# Controller_Board_Interface.net
KiCad netlist of a schematic drawn in Altium Designer
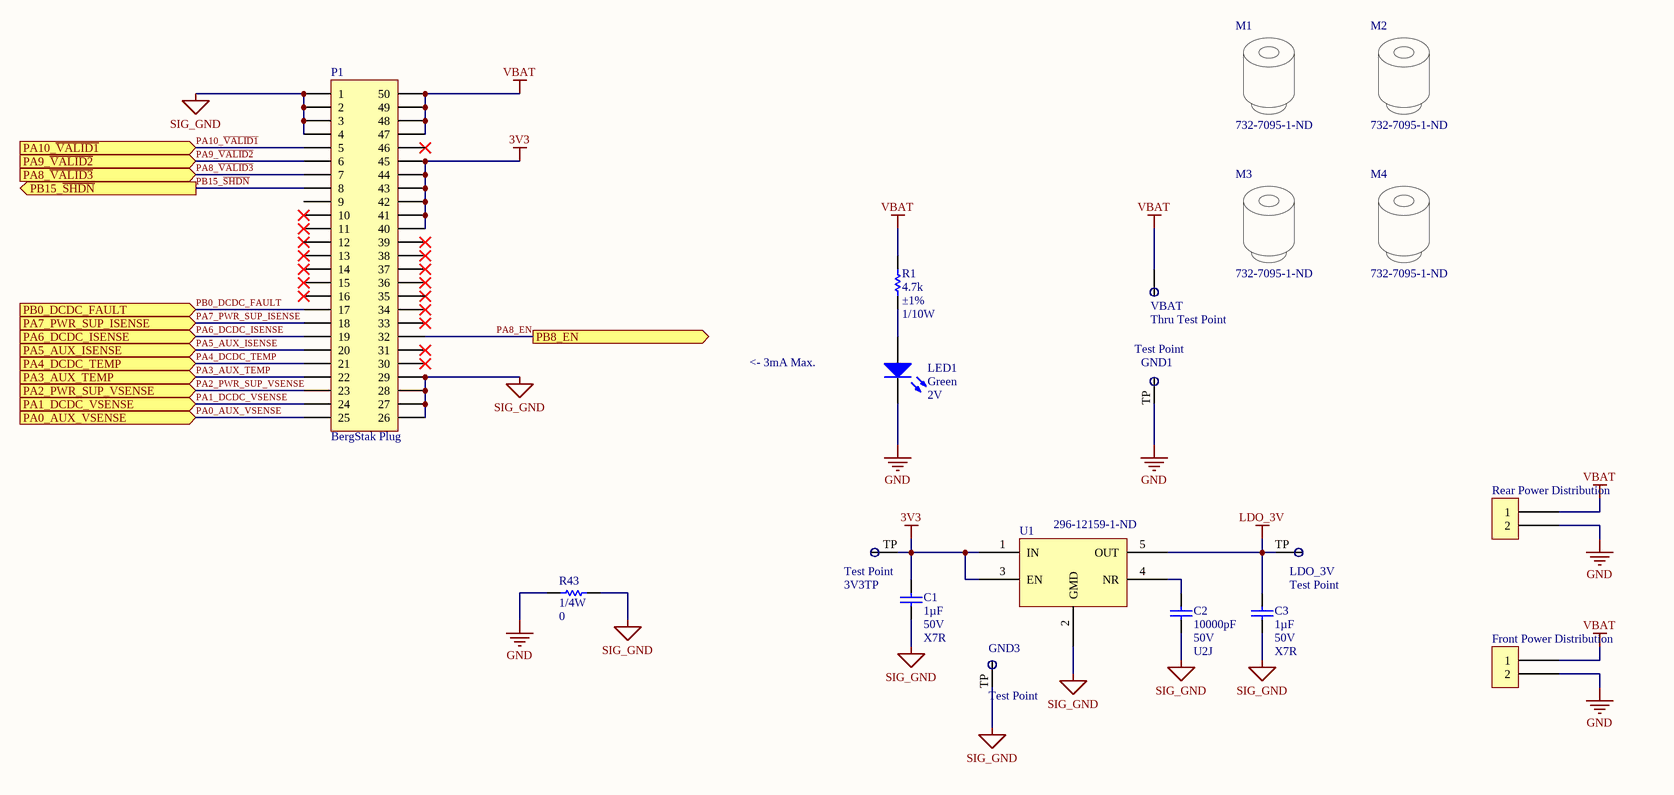
[diagram p0: Controller_Board_Interface.SchDoc]

(export (version "E")
  (design (tool "Eeschema 10.0.6"))
  (components
    (comp (ref "3V3TP")
      (value "Test Point")
      (footprint "Test Point")
      (libsource (lib "Schematic Diagrams") (part "Test Point"))
    )
    (comp (ref "C1")
      (value "CAP CER 1UF 50V 10% X7R 0603")
      (footprint "CAP, 0603")
      (description "1µF ±10% 50V Ceramic Capacitor X7R 0603 (1608 Metric)")
      (fields
        (field (name "TOLERANCE") "±10%")
        (field (name "CAPACITANCE") "1µF")
        (field (name "VOLTAGE") "50V")
        (field (name "TEMPERATURE COEFFICIENT") "X7R")
      )
      (libsource (lib "Schematic Diagrams") (part "CAP CER 1UF 50V 10% X7R 0603"))
    )
    (comp (ref "C2")
      (value "CAP CER 10nF 50V 5% X7R 0603")
      (footprint "CAP, 0603")
      (description "10000pF ±5% 50V Ceramic Capacitor U2J 0603 (1608 Metric)")
      (fields
        (field (name "TOLERANCE") "±5%")
        (field (name "CAPACITANCE") "10000pF")
        (field (name "VOLTAGE") "50V")
        (field (name "TEMPERATURE COEFFICIENT") "U2J")
      )
      (libsource (lib "Schematic Diagrams") (part "CAP CER 10nF 50V 5% X7R 0603"))
    )
    (comp (ref "C3")
      (value "CAP CER 1UF 50V 10% X7R 0603")
      (footprint "CAP, 0603")
      (description "1µF ±10% 50V Ceramic Capacitor X7R 0603 (1608 Metric)")
      (fields
        (field (name "TOLERANCE") "±10%")
        (field (name "CAPACITANCE") "1µF")
        (field (name "VOLTAGE") "50V")
        (field (name "TEMPERATURE COEFFICIENT") "X7R")
      )
      (libsource (lib "Schematic Diagrams") (part "CAP CER 1UF 50V 10% X7R 0603"))
    )
    (comp (ref "Front Power Distribution")
      (value "CONN HEADER TE  ELCON Mini 2POS PCB")
      (footprint "CONN HEADER TE  ELCON Mini 2POS PCB-Footprint-1")
      (description "CONN HEADER 2POS PCB")
      (libsource (lib "University of Waterloo - Solar Car Team") (part "CONN HEADER TE  ELCON Mini 2POS PCB"))
    )
    (comp (ref "GND1")
      (value "Test Point")
      (footprint "Test Point")
      (libsource (lib "Schematic Diagrams") (part "Test Point"))
    )
    (comp (ref "GND3")
      (value "Test Point")
      (footprint "Test Point")
      (libsource (lib "Schematic Diagrams") (part "Test Point"))
    )
    (comp (ref "LDO_3V")
      (value "Test Point")
      (footprint "Test Point")
      (libsource (lib "Schematic Diagrams") (part "Test Point"))
    )
    (comp (ref "LED1")
      (value "LED GREEN CLEAR 2V 0603")
      (footprint "LED_0603")
      (description "Green 572nm LED Indication - Discrete 2V 0603 (1608 Metric)")
      (fields
        (field (name "COLOR") "Green")
        (field (name "VOLTAGE - FORWARD (VF) (TYP)") "2V")
        (field (name "MANUFACTURER") "Wurth Electronics Inc.")
        (field (name "MANUFACTURER PART NUMBER") "150060VS75000")
      )
      (libsource (lib "Schematic Diagrams") (part "LED GREEN CLEAR 2V 0603"))
    )
    (comp (ref "M1")
      (value "STANDOFF RND M2.5X0.45 STEEL 5MM")
      (footprint "M2.5 Standoff")
      (fields
        (field (name "MANUFACTURER") "Wurth Electronics")
        (field (name "MANUFACTURER PART NUMBER") "9774050151R")
        (field (name "SUPPLIER PART NUMBER 1") "732-7095-1-ND")
      )
      (libsource (lib "Schematic Diagrams") (part "STANDOFF RND M2.5X0.45 STEEL 5MM"))
    )
    (comp (ref "M2")
      (value "STANDOFF RND M2.5X0.45 STEEL 5MM")
      (footprint "M2.5 Standoff")
      (fields
        (field (name "MANUFACTURER") "Wurth Electronics")
        (field (name "MANUFACTURER PART NUMBER") "9774050151R")
        (field (name "SUPPLIER PART NUMBER 1") "732-7095-1-ND")
      )
      (libsource (lib "Schematic Diagrams") (part "STANDOFF RND M2.5X0.45 STEEL 5MM"))
    )
    (comp (ref "M3")
      (value "STANDOFF RND M2.5X0.45 STEEL 5MM")
      (footprint "M2.5 Standoff")
      (fields
        (field (name "MANUFACTURER") "Wurth Electronics")
        (field (name "MANUFACTURER PART NUMBER") "9774050151R")
        (field (name "SUPPLIER PART NUMBER 1") "732-7095-1-ND")
      )
      (libsource (lib "Schematic Diagrams") (part "STANDOFF RND M2.5X0.45 STEEL 5MM"))
    )
    (comp (ref "M4")
      (value "STANDOFF RND M2.5X0.45 STEEL 5MM")
      (footprint "M2.5 Standoff")
      (fields
        (field (name "MANUFACTURER") "Wurth Electronics")
        (field (name "MANUFACTURER PART NUMBER") "9774050151R")
        (field (name "SUPPLIER PART NUMBER 1") "732-7095-1-ND")
      )
      (libsource (lib "Schematic Diagrams") (part "STANDOFF RND M2.5X0.45 STEEL 5MM"))
    )
    (comp (ref "P1")
      (value "CONN 50POS Bergstak Plug 0.02\"")
      (footprint "CONN, Bergstak 50 Pos Plug")
      (description "50 Position Connector Plug, Outer Shroud Contacts Surface Mount Gold")
      (fields (field (name "SERIES") "BergStak Plug"))
      (libsource (lib "Schematic Diagrams") (part "CONN 50POS Bergstak Plug 0.02{dblquote}"))
    )
    (comp (ref "R1")
      (value "RES 4.7K OHM 1% 1/10W 0603")
      (footprint "RES, 0603")
      (description "4.7k Ohm ±1% 0.1W, 1/10W Chip Resistor 0603 (1608 Metric) Moisture Resistant Thick Film")
      (fields
        (field (name "RESISTANCE (OHMS)") "4.7k")
        (field (name "TOLERANCE") "±1%")
        (field (name "POWER (WATTS)") "1/10W")
      )
      (libsource (lib "Schematic Diagrams") (part "RES 4.7K OHM 1% 1/10W 0603"))
    )
    (comp (ref "R43")
      (value "0")
      (footprint "RES, 0603")
      (description "RES SMD 0.0 OHM JUMPER 1/4W 0603")
      (fields
        (field (name "POWER (WATTS)") "1/4W")
        (field (name "Comment") "RES 0.0 OHM 1/4W 0603")
        (field (name "SOURCE") "Schematic Diagrams.SchLib")
      )
      (libsource (lib "University of Waterloo - Solar Car Team") (part "Symbol"))
    )
    (comp (ref "Rear Power Distribution")
      (value "CONN HEADER TE  ELCON Mini 2POS PCB")
      (footprint "CONN HEADER TE  ELCON Mini 2POS PCB-Footprint-1")
      (description "CONN HEADER 2POS PCB")
      (libsource (lib "University of Waterloo - Solar Car Team") (part "CONN HEADER TE  ELCON Mini 2POS PCB"))
    )
    (comp (ref "U1")
      (value "IC REG LINEAR 3V 200MA SOT23-5")
      (footprint "SOT95P280X145-5N")
      (description "Linear Voltage Regulator IC 1 Output 200mA SOT-23-5")
      (fields (field (name "SUPPLIER PART NUMBER 1") "296-12159-1-ND"))
      (libsource (lib "Schematic Diagrams") (part "IC REG LINEAR 3V 200MA SOT23-5"))
    )
    (comp (ref "VBAT")
      (value "Thru Test Point")
      (footprint "Thru Test Point")
      (libsource (lib "Schematic Diagrams") (part "Thru Test Point"))
    )
  )
  (nets
    (net (code "1") (name "/PA0_AUX_VSENSE") (class "Default")
      (node (ref "P1") (pin "25") (pinfunction "25_25") (pintype "passive"))
    )
    (net (code "2") (name "/PA1_DCDC_VSENSE") (class "Default")
      (node (ref "P1") (pin "24") (pinfunction "24_24") (pintype "passive"))
    )
    (net (code "3") (name "/PA2_PWR_SUP_VSENSE") (class "Default")
      (node (ref "P1") (pin "23") (pinfunction "23_23") (pintype "passive"))
    )
    (net (code "4") (name "/PA3_AUX_TEMP") (class "Default")
      (node (ref "P1") (pin "22") (pinfunction "22_22") (pintype "passive"))
    )
    (net (code "5") (name "/PA4_DCDC_TEMP") (class "Default")
      (node (ref "P1") (pin "21") (pinfunction "21_21") (pintype "passive"))
    )
    (net (code "6") (name "/PA5_AUX_ISENSE") (class "Default")
      (node (ref "P1") (pin "20") (pinfunction "20_20") (pintype "passive"))
    )
    (net (code "7") (name "/PA6_DCDC_ISENSE") (class "Default")
      (node (ref "P1") (pin "19") (pinfunction "19_19") (pintype "passive"))
    )
    (net (code "8") (name "/PA7_PWR_SUP_ISENSE") (class "Default")
      (node (ref "P1") (pin "18") (pinfunction "18_18") (pintype "passive"))
    )
    (net (code "9") (name "/PA8_EN") (class "Default")
      (node (ref "P1") (pin "32") (pinfunction "32_32") (pintype "passive"))
    )
    (net (code "10") (name "/PA8_~{VALID3}") (class "Default")
      (node (ref "P1") (pin "7") (pinfunction "7_7") (pintype "passive"))
    )
    (net (code "11") (name "/PA9_~{VALID2}") (class "Default")
      (node (ref "P1") (pin "6") (pinfunction "6_6") (pintype "passive"))
    )
    (net (code "12") (name "/PA10_~{VALID1}") (class "Default")
      (node (ref "P1") (pin "5") (pinfunction "5_5") (pintype "passive"))
    )
    (net (code "13") (name "/PB0_DCDC_FAULT") (class "Default")
      (node (ref "P1") (pin "17") (pinfunction "17_17") (pintype "passive"))
    )
    (net (code "14") (name "/PB15_~{SHDN}") (class "Default")
      (node (ref "P1") (pin "8") (pinfunction "8_8") (pintype "passive"))
    )
    (net (code "15") (name "3V3") (class "Default")
      (node (ref "3V3TP") (pin "TP") (pinfunction "1_TP") (pintype "passive"))
      (node (ref "C1") (pin "1") (pinfunction "1_1") (pintype "passive"))
      (node (ref "P1") (pin "40") (pinfunction "40_40") (pintype "passive"))
      (node (ref "P1") (pin "41") (pinfunction "41_41") (pintype "passive"))
      (node (ref "P1") (pin "42") (pinfunction "42_42") (pintype "passive"))
      (node (ref "P1") (pin "43") (pinfunction "43_43") (pintype "passive"))
      (node (ref "P1") (pin "44") (pinfunction "44_44") (pintype "passive"))
      (node (ref "P1") (pin "45") (pinfunction "45_45") (pintype "passive"))
      (node (ref "U1") (pin "1") (pinfunction "IN_1") (pintype "passive"))
      (node (ref "U1") (pin "3") (pinfunction "EN_3") (pintype "passive"))
    )
    (net (code "16") (name "GND") (class "Default")
      (node (ref "Front Power Distribution") (pin "2") (pinfunction "2_2") (pintype "passive"))
      (node (ref "GND1") (pin "TP") (pinfunction "1_TP") (pintype "passive"))
      (node (ref "LED1") (pin "2") (pinfunction "K_2") (pintype "passive"))
      (node (ref "R43") (pin "1") (pinfunction "1_1") (pintype "passive"))
      (node (ref "Rear Power Distribution") (pin "2") (pinfunction "2_2") (pintype "passive"))
    )
    (net (code "17") (name "LDO_3V") (class "Default")
      (node (ref "C3") (pin "1") (pinfunction "1_1") (pintype "passive"))
      (node (ref "LDO_3V") (pin "TP") (pinfunction "1_TP") (pintype "passive"))
      (node (ref "U1") (pin "5") (pinfunction "OUT_5") (pintype "passive"))
    )
    (net (code "18") (name "Net-(LED1-A)") (class "Default")
      (node (ref "LED1") (pin "1") (pinfunction "A_1") (pintype "passive"))
      (node (ref "R1") (pin "2") (pinfunction "2_2") (pintype "passive"))
    )
    (net (code "19") (name "Net-(U1-NR)") (class "Default")
      (node (ref "C2") (pin "1") (pinfunction "1_1") (pintype "passive"))
      (node (ref "U1") (pin "4") (pinfunction "NR_4") (pintype "passive"))
    )
    (net (code "20") (name "SIG_GND") (class "Default")
      (node (ref "C1") (pin "2") (pinfunction "2_2") (pintype "passive"))
      (node (ref "C2") (pin "2") (pinfunction "2_2") (pintype "passive"))
      (node (ref "C3") (pin "2") (pinfunction "2_2") (pintype "passive"))
      (node (ref "GND3") (pin "TP") (pinfunction "1_TP") (pintype "passive"))
      (node (ref "P1") (pin "1") (pinfunction "1_1") (pintype "passive"))
      (node (ref "P1") (pin "2") (pinfunction "2_2") (pintype "passive"))
      (node (ref "P1") (pin "26") (pinfunction "26_26") (pintype "passive"))
      (node (ref "P1") (pin "27") (pinfunction "27_27") (pintype "passive"))
      (node (ref "P1") (pin "28") (pinfunction "28_28") (pintype "passive"))
      (node (ref "P1") (pin "29") (pinfunction "29_29") (pintype "passive"))
      (node (ref "P1") (pin "3") (pinfunction "3_3") (pintype "passive"))
      (node (ref "P1") (pin "4") (pinfunction "4_4") (pintype "passive"))
      (node (ref "R43") (pin "2") (pinfunction "2_2") (pintype "passive"))
      (node (ref "U1") (pin "2") (pinfunction "GMD_2") (pintype "passive"))
    )
    (net (code "21") (name "VBAT") (class "Default")
      (node (ref "Front Power Distribution") (pin "1") (pinfunction "1_1") (pintype "passive"))
      (node (ref "P1") (pin "47") (pinfunction "47_47") (pintype "passive"))
      (node (ref "P1") (pin "48") (pinfunction "48_48") (pintype "passive"))
      (node (ref "P1") (pin "49") (pinfunction "49_49") (pintype "passive"))
      (node (ref "P1") (pin "50") (pinfunction "50_50") (pintype "passive"))
      (node (ref "R1") (pin "1") (pinfunction "1_1") (pintype "passive"))
      (node (ref "Rear Power Distribution") (pin "1") (pinfunction "1_1") (pintype "passive"))
      (node (ref "VBAT") (pin "TH_TP") (pinfunction "1_TH_TP") (pintype "passive"))
    )
    (net (code "22") (name "unconnected-(P1-Pad9)") (class "Default")
      (node (ref "P1") (pin "9") (pinfunction "9_9") (pintype "passive"))
    )
    (net (code "23") (name "unconnected-(P1-Pad10)") (class "Default")
      (node (ref "P1") (pin "10") (pinfunction "10_10") (pintype "passive+no_connect"))
    )
    (net (code "24") (name "unconnected-(P1-Pad11)") (class "Default")
      (node (ref "P1") (pin "11") (pinfunction "11_11") (pintype "passive+no_connect"))
    )
    (net (code "25") (name "unconnected-(P1-Pad12)") (class "Default")
      (node (ref "P1") (pin "12") (pinfunction "12_12") (pintype "passive+no_connect"))
    )
    (net (code "26") (name "unconnected-(P1-Pad13)") (class "Default")
      (node (ref "P1") (pin "13") (pinfunction "13_13") (pintype "passive+no_connect"))
    )
    (net (code "27") (name "unconnected-(P1-Pad14)") (class "Default")
      (node (ref "P1") (pin "14") (pinfunction "14_14") (pintype "passive+no_connect"))
    )
    (net (code "28") (name "unconnected-(P1-Pad15)") (class "Default")
      (node (ref "P1") (pin "15") (pinfunction "15_15") (pintype "passive+no_connect"))
    )
    (net (code "29") (name "unconnected-(P1-Pad16)") (class "Default")
      (node (ref "P1") (pin "16") (pinfunction "16_16") (pintype "passive+no_connect"))
    )
    (net (code "30") (name "unconnected-(P1-Pad30)") (class "Default")
      (node (ref "P1") (pin "30") (pinfunction "30_30") (pintype "passive+no_connect"))
    )
    (net (code "31") (name "unconnected-(P1-Pad31)") (class "Default")
      (node (ref "P1") (pin "31") (pinfunction "31_31") (pintype "passive+no_connect"))
    )
    (net (code "32") (name "unconnected-(P1-Pad33)") (class "Default")
      (node (ref "P1") (pin "33") (pinfunction "33_33") (pintype "passive+no_connect"))
    )
    (net (code "33") (name "unconnected-(P1-Pad34)") (class "Default")
      (node (ref "P1") (pin "34") (pinfunction "34_34") (pintype "passive+no_connect"))
    )
    (net (code "34") (name "unconnected-(P1-Pad35)") (class "Default")
      (node (ref "P1") (pin "35") (pinfunction "35_35") (pintype "passive+no_connect"))
    )
    (net (code "35") (name "unconnected-(P1-Pad36)") (class "Default")
      (node (ref "P1") (pin "36") (pinfunction "36_36") (pintype "passive+no_connect"))
    )
    (net (code "36") (name "unconnected-(P1-Pad37)") (class "Default")
      (node (ref "P1") (pin "37") (pinfunction "37_37") (pintype "passive+no_connect"))
    )
    (net (code "37") (name "unconnected-(P1-Pad38)") (class "Default")
      (node (ref "P1") (pin "38") (pinfunction "38_38") (pintype "passive+no_connect"))
    )
    (net (code "38") (name "unconnected-(P1-Pad39)") (class "Default")
      (node (ref "P1") (pin "39") (pinfunction "39_39") (pintype "passive+no_connect"))
    )
    (net (code "39") (name "unconnected-(P1-Pad46)") (class "Default")
      (node (ref "P1") (pin "46") (pinfunction "46_46") (pintype "passive+no_connect"))
    )
  )
)
